# lcd-i2c.net
KiCad netlist of a schematic drawn in EAGLE
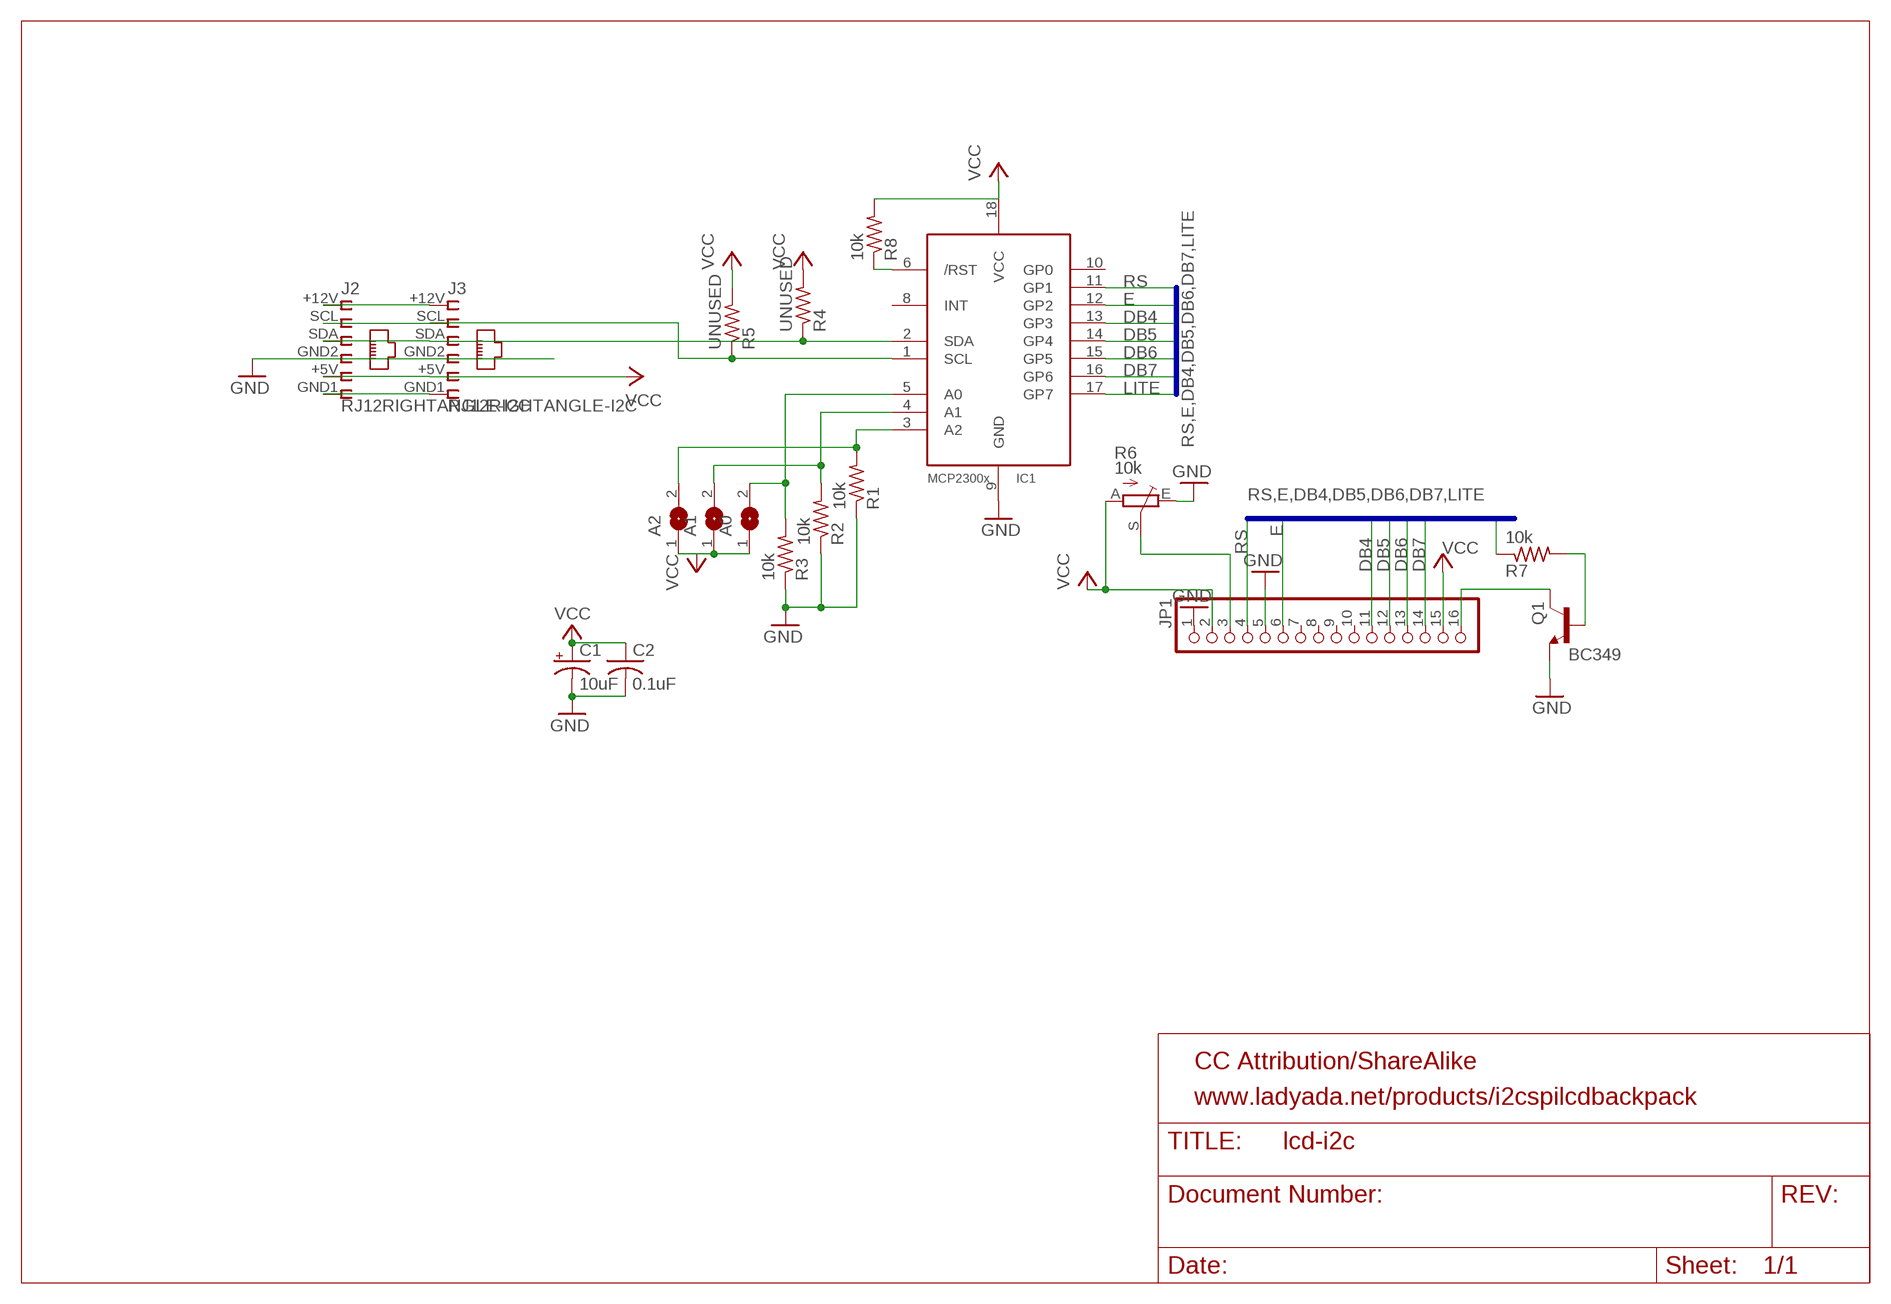
[diagram p0: schematic, sheet 1]

(export (version "E")
  (design (tool "Eeschema 10.0.6"))
  (components
    (comp (ref "A0") (value "SJ") (footprint "eagle-import:SJ") (libsource (lib "eagle-import") (part "SJ")))
    (comp (ref "A1") (value "SJ") (footprint "eagle-import:SJ") (libsource (lib "eagle-import") (part "SJ")))
    (comp (ref "A2") (value "SJ") (footprint "eagle-import:SJ") (libsource (lib "eagle-import") (part "SJ")))
    (comp (ref "C1")
      (value "10uF")
      (footprint "eagle-import:A_3216-18R")
      (libsource (lib "eagle-import") (part "CPOL-USA/3216-18R"))
    )
    (comp (ref "C2")
      (value "0.1uF")
      (footprint "eagle-import:C1206")
      (libsource (lib "eagle-import") (part "C-USC1206"))
    )
    (comp (ref "IC1")
      (value "MCP2300X/P")
      (footprint "eagle-import:DIL18")
      (libsource (lib "eagle-import") (part "MCP2300X/P"))
    )
    (comp (ref "J2")
      (value "RJ12RIGHTANGLE-I2C")
      (footprint "eagle-import:RJ12-RIGHTANGLE-I2C")
      (libsource (lib "eagle-import") (part "RJ12RIGHTANGLE-I2C"))
    )
    (comp (ref "J3")
      (value "RJ12RIGHTANGLE-I2C")
      (footprint "eagle-import:RJ12-RIGHTANGLE-I2C")
      (libsource (lib "eagle-import") (part "RJ12RIGHTANGLE-I2C"))
    )
    (comp (ref "JP1")
      (value "PINHD-1X16")
      (footprint "eagle-import:1X16")
      (libsource (lib "eagle-import") (part "PINHD-1X16"))
    )
    (comp (ref "Q1")
      (value "BC349")
      (footprint "eagle-import:TO92-EBC")
      (libsource (lib "eagle-import") (part "-NPN-TO92-EBCBC317"))
    )
    (comp (ref "R1")
      (value "10k")
      (footprint "eagle-import:M1206")
      (libsource (lib "eagle-import") (part "R-US_M1206"))
    )
    (comp (ref "R2")
      (value "10k")
      (footprint "eagle-import:M1206")
      (libsource (lib "eagle-import") (part "R-US_M1206"))
    )
    (comp (ref "R3")
      (value "10k")
      (footprint "eagle-import:M1206")
      (libsource (lib "eagle-import") (part "R-US_M1206"))
    )
    (comp (ref "R4")
      (value "UNUSED")
      (footprint "eagle-import:M1206")
      (libsource (lib "eagle-import") (part "R-US_M1206"))
    )
    (comp (ref "R5")
      (value "UNUSED")
      (footprint "eagle-import:M1206")
      (libsource (lib "eagle-import") (part "R-US_M1206"))
    )
    (comp (ref "R6")
      (value "10k")
      (footprint "eagle-import:CA6V")
      (libsource (lib "eagle-import") (part "TRIM_EU-CA6V"))
    )
    (comp (ref "R7")
      (value "10k")
      (footprint "eagle-import:M1206")
      (libsource (lib "eagle-import") (part "R-US_M1206"))
    )
    (comp (ref "R8")
      (value "10k")
      (footprint "eagle-import:M1206")
      (libsource (lib "eagle-import") (part "R-US_M1206"))
    )
  )
  (nets
    (net (code "1") (name "/DB4") (class "Default")
      (node (ref "IC1") (pin "13") (pinfunction "GP3_13") (pintype "bidirectional"))
      (node (ref "JP1") (pin "11") (pinfunction "11_11") (pintype "passive"))
    )
    (net (code "2") (name "/DB5") (class "Default")
      (node (ref "IC1") (pin "14") (pinfunction "GP4_14") (pintype "bidirectional"))
      (node (ref "JP1") (pin "12") (pinfunction "12_12") (pintype "passive"))
    )
    (net (code "3") (name "/DB6") (class "Default")
      (node (ref "IC1") (pin "15") (pinfunction "GP5_15") (pintype "bidirectional"))
      (node (ref "JP1") (pin "13") (pinfunction "13_13") (pintype "passive"))
    )
    (net (code "4") (name "/DB7") (class "Default")
      (node (ref "IC1") (pin "16") (pinfunction "GP6_16") (pintype "bidirectional"))
      (node (ref "JP1") (pin "14") (pinfunction "14_14") (pintype "passive"))
    )
    (net (code "5") (name "/E") (class "Default")
      (node (ref "IC1") (pin "12") (pinfunction "GP2_12") (pintype "bidirectional"))
      (node (ref "JP1") (pin "6") (pinfunction "6_6") (pintype "passive"))
    )
    (net (code "6") (name "/LITE") (class "Default")
      (node (ref "IC1") (pin "17") (pinfunction "GP7_17") (pintype "bidirectional"))
      (node (ref "R7") (pin "1") (pinfunction "1_1") (pintype "passive"))
    )
    (net (code "7") (name "/RS") (class "Default")
      (node (ref "IC1") (pin "11") (pinfunction "GP1_11") (pintype "bidirectional"))
      (node (ref "JP1") (pin "4") (pinfunction "4_4") (pintype "passive"))
    )
    (net (code "9") (name "GND") (class "Default")
      (node (ref "C1") (pin "-") (pinfunction "-_-") (pintype "passive"))
      (node (ref "C2") (pin "2") (pinfunction "2_2") (pintype "passive"))
      (node (ref "IC1") (pin "9") (pinfunction "GND_9") (pintype "power_in"))
      (node (ref "J2") (pin "GND2") (pinfunction "4_GND2") (pintype "bidirectional"))
      (node (ref "J3") (pin "GND2") (pinfunction "4_GND2") (pintype "bidirectional"))
      (node (ref "JP1") (pin "1") (pinfunction "1_1") (pintype "passive"))
      (node (ref "JP1") (pin "5") (pinfunction "5_5") (pintype "passive"))
      (node (ref "Q1") (pin "E") (pinfunction "E_E") (pintype "passive"))
      (node (ref "R1") (pin "1") (pinfunction "1_1") (pintype "passive"))
      (node (ref "R2") (pin "1") (pinfunction "1_1") (pintype "passive"))
      (node (ref "R3") (pin "1") (pinfunction "1_1") (pintype "passive"))
      (node (ref "R6") (pin "E") (pinfunction "E_E") (pintype "passive"))
    )
    (net (code "10") (name "Net-(IC1-A0)") (class "Default")
      (node (ref "A0") (pin "2") (pinfunction "2_2") (pintype "passive"))
      (node (ref "IC1") (pin "5") (pinfunction "A0_5") (pintype "input"))
      (node (ref "R3") (pin "2") (pinfunction "2_2") (pintype "passive"))
    )
    (net (code "11") (name "Net-(IC1-A1)") (class "Default")
      (node (ref "A1") (pin "2") (pinfunction "2_2") (pintype "passive"))
      (node (ref "IC1") (pin "4") (pinfunction "A1_4") (pintype "input"))
      (node (ref "R2") (pin "2") (pinfunction "2_2") (pintype "passive"))
    )
    (net (code "12") (name "Net-(IC1-A2)") (class "Default")
      (node (ref "A2") (pin "2") (pinfunction "2_2") (pintype "passive"))
      (node (ref "IC1") (pin "3") (pinfunction "A2_3") (pintype "input"))
      (node (ref "R1") (pin "2") (pinfunction "2_2") (pintype "passive"))
    )
    (net (code "13") (name "Net-(IC1-SCL)") (class "Default")
      (node (ref "IC1") (pin "1") (pinfunction "SCL_1") (pintype "bidirectional"))
      (node (ref "J2") (pin "SCL") (pinfunction "2_SCL") (pintype "bidirectional"))
      (node (ref "J3") (pin "SCL") (pinfunction "2_SCL") (pintype "bidirectional"))
      (node (ref "R5") (pin "1") (pinfunction "1_1") (pintype "passive"))
    )
    (net (code "14") (name "Net-(IC1-SDA)") (class "Default")
      (node (ref "IC1") (pin "2") (pinfunction "SDA_2") (pintype "bidirectional"))
      (node (ref "J2") (pin "SDA") (pinfunction "3_SDA") (pintype "bidirectional"))
      (node (ref "J3") (pin "SDA") (pinfunction "3_SDA") (pintype "bidirectional"))
      (node (ref "R4") (pin "1") (pinfunction "1_1") (pintype "passive"))
    )
    (net (code "15") (name "Net-(IC1-{slash}RST)") (class "Default")
      (node (ref "IC1") (pin "6") (pinfunction "/RST_6") (pintype "input"))
      (node (ref "R8") (pin "1") (pinfunction "1_1") (pintype "passive"))
    )
    (net (code "16") (name "Net-(J2-1)") (class "Default")
      (node (ref "J2") (pin "+12V") (pinfunction "1_+12V") (pintype "bidirectional"))
      (node (ref "J3") (pin "+12V") (pinfunction "1_+12V") (pintype "bidirectional"))
    )
    (net (code "17") (name "Net-(J2-6)") (class "Default")
      (node (ref "J2") (pin "GND1") (pinfunction "6_GND1") (pintype "bidirectional"))
      (node (ref "J3") (pin "GND1") (pinfunction "6_GND1") (pintype "bidirectional"))
    )
    (net (code "18") (name "Net-(JP1-Pad3)") (class "Default")
      (node (ref "JP1") (pin "3") (pinfunction "3_3") (pintype "passive"))
      (node (ref "R6") (pin "S") (pinfunction "S_S") (pintype "passive"))
    )
    (net (code "19") (name "Net-(JP1-Pad16)") (class "Default")
      (node (ref "JP1") (pin "16") (pinfunction "16_16") (pintype "passive"))
      (node (ref "Q1") (pin "C") (pinfunction "C_C") (pintype "passive"))
    )
    (net (code "20") (name "Net-(Q1-PadB)") (class "Default")
      (node (ref "Q1") (pin "B") (pinfunction "B_B") (pintype "passive"))
      (node (ref "R7") (pin "2") (pinfunction "2_2") (pintype "passive"))
    )
    (net (code "21") (name "VCC") (class "Default")
      (node (ref "A0") (pin "1") (pinfunction "1_1") (pintype "passive"))
      (node (ref "A1") (pin "1") (pinfunction "1_1") (pintype "passive"))
      (node (ref "A2") (pin "1") (pinfunction "1_1") (pintype "passive"))
      (node (ref "C1") (pin "+") (pinfunction "+_+") (pintype "passive"))
      (node (ref "C2") (pin "1") (pinfunction "1_1") (pintype "passive"))
      (node (ref "IC1") (pin "18") (pinfunction "VCC_18") (pintype "power_in"))
      (node (ref "J2") (pin "+5V") (pinfunction "5_+5V") (pintype "bidirectional"))
      (node (ref "J3") (pin "+5V") (pinfunction "5_+5V") (pintype "bidirectional"))
      (node (ref "JP1") (pin "15") (pinfunction "15_15") (pintype "passive"))
      (node (ref "JP1") (pin "2") (pinfunction "2_2") (pintype "passive"))
      (node (ref "R4") (pin "2") (pinfunction "2_2") (pintype "passive"))
      (node (ref "R5") (pin "2") (pinfunction "2_2") (pintype "passive"))
      (node (ref "R6") (pin "A") (pinfunction "A_A") (pintype "passive"))
      (node (ref "R8") (pin "2") (pinfunction "2_2") (pintype "passive"))
    )
    (net (code "22") (name "unconnected-(IC1-GP0-Pad10)") (class "Default")
      (node (ref "IC1") (pin "10") (pinfunction "GP0_10") (pintype "bidirectional"))
    )
    (net (code "23") (name "unconnected-(IC1-INT-Pad8)") (class "Default")
      (node (ref "IC1") (pin "8") (pinfunction "INT_8") (pintype "output"))
    )
    (net (code "24") (name "unconnected-(JP1-Pad7)") (class "Default")
      (node (ref "JP1") (pin "7") (pinfunction "7_7") (pintype "passive"))
    )
    (net (code "25") (name "unconnected-(JP1-Pad8)") (class "Default")
      (node (ref "JP1") (pin "8") (pinfunction "8_8") (pintype "passive"))
    )
    (net (code "26") (name "unconnected-(JP1-Pad9)") (class "Default")
      (node (ref "JP1") (pin "9") (pinfunction "9_9") (pintype "passive"))
    )
    (net (code "27") (name "unconnected-(JP1-Pad10)") (class "Default")
      (node (ref "JP1") (pin "10") (pinfunction "10_10") (pintype "passive"))
    )
  )
)
